# RF_STM.net
KiCad netlist of a schematic drawn in Altium Designer
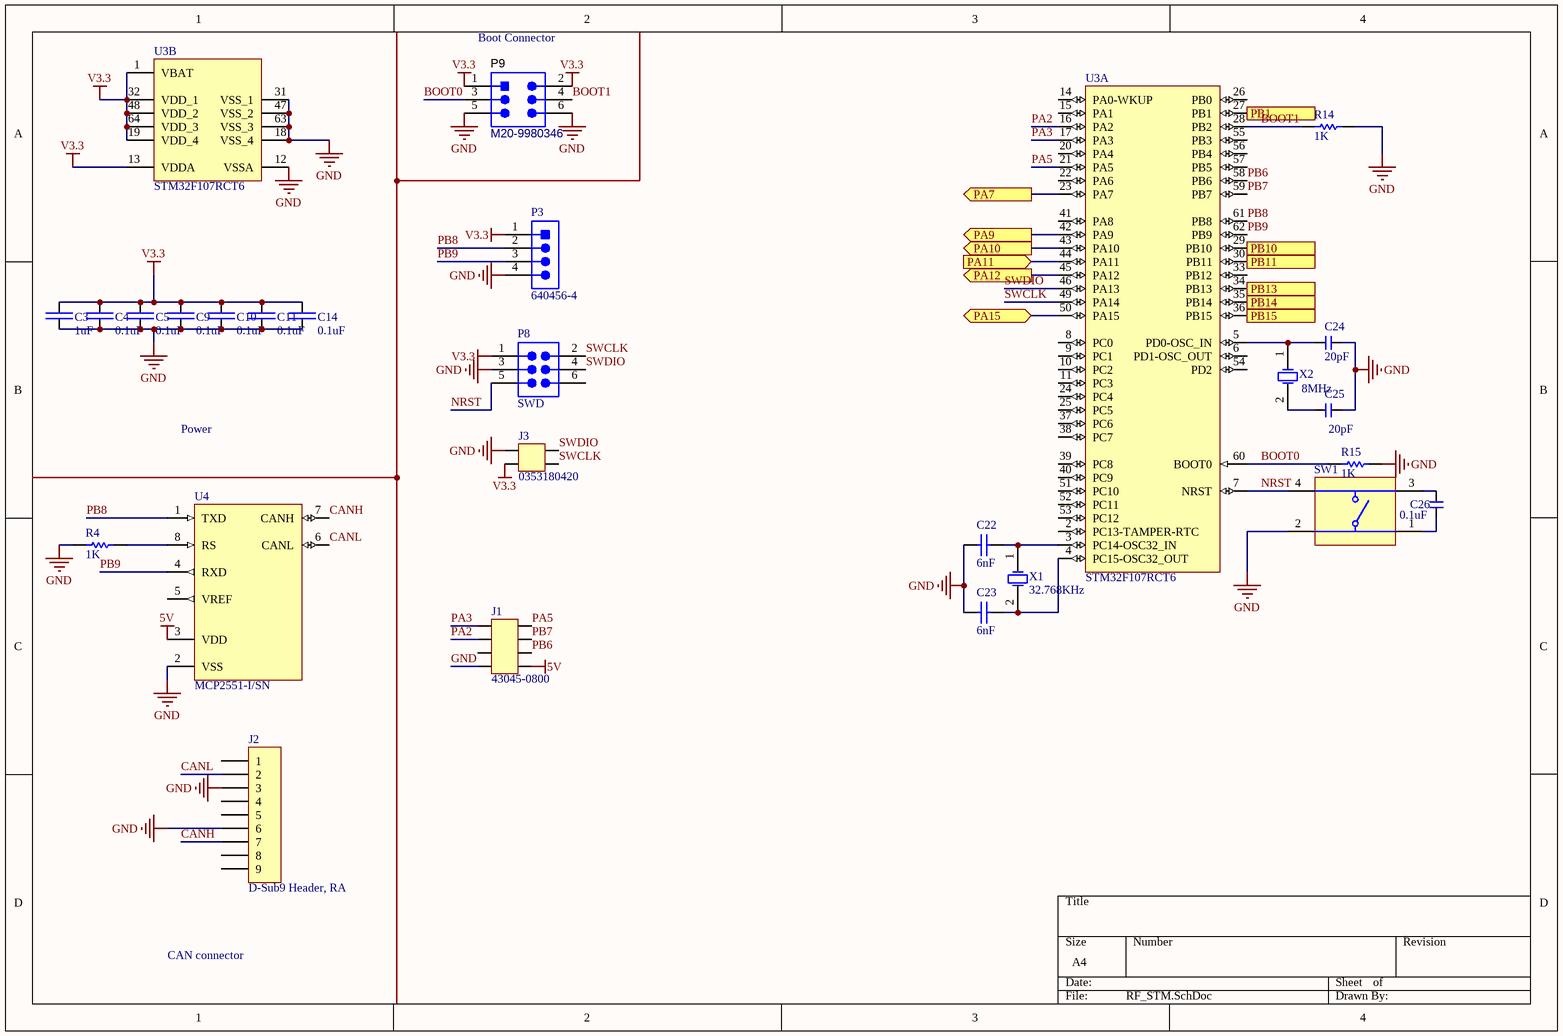
[diagram p0: RF_STM.SchDoc]

(export (version "E")
  (design (tool "Eeschema 10.0.6"))
  (components
    (comp (ref "C3")
      (value "1uF")
      (footprint "C0805")
      (description "Cap Ceramic 1uF 25V X7R 10% SMD 0805 125C T/R")
      (fields
        (field (name "MANUFACTURER") "Samsung")
        (field (name "MANUFACTURER PART NUMBER") "CL21B105KAFNNNE")
      )
      (libsource (lib "Capacitors") (part "CL21B105KAFNNNE"))
    )
    (comp (ref "C4")
      (value "0.1uF")
      (footprint "C0805")
      (description "CAP CER 0.1UF 50V X7R 0805")
      (fields
        (field (name "MANUFACTURER") "Samsung")
        (field (name "MANUFACTURER PART NUMBER") "CL21B104KBCWPNC")
      )
      (libsource (lib "Capacitors") (part "CL21B104KBCWPNC"))
    )
    (comp (ref "C5")
      (value "0.1uF")
      (footprint "C0805")
      (description "CAP CER 0.1UF 50V X7R 0805")
      (fields
        (field (name "MANUFACTURER") "Samsung")
        (field (name "MANUFACTURER PART NUMBER") "CL21B104KBCWPNC")
      )
      (libsource (lib "Capacitors") (part "CL21B104KBCWPNC"))
    )
    (comp (ref "C9")
      (value "0.1uF")
      (footprint "C0805")
      (description "CAP CER 0.1UF 50V X7R 0805")
      (fields
        (field (name "MANUFACTURER") "Samsung")
        (field (name "MANUFACTURER PART NUMBER") "CL21B104KBCWPNC")
      )
      (libsource (lib "Capacitors") (part "CL21B104KBCWPNC"))
    )
    (comp (ref "C10")
      (value "0.1uF")
      (footprint "C0805")
      (description "CAP CER 0.1UF 50V X7R 0805")
      (fields
        (field (name "MANUFACTURER") "Samsung")
        (field (name "MANUFACTURER PART NUMBER") "CL21B104KBCWPNC")
      )
      (libsource (lib "Capacitors") (part "CL21B104KBCWPNC"))
    )
    (comp (ref "C11")
      (value "0.1uF")
      (footprint "C0805")
      (description "CAP CER 0.1UF 50V X7R 0805")
      (fields
        (field (name "MANUFACTURER") "Samsung")
        (field (name "MANUFACTURER PART NUMBER") "CL21B104KBCWPNC")
      )
      (libsource (lib "Capacitors") (part "CL21B104KBCWPNC"))
    )
    (comp (ref "C14")
      (value "0.1uF")
      (footprint "C0805")
      (description "CAP CER 0.1UF 50V X7R 0805")
      (fields
        (field (name "MANUFACTURER") "Samsung")
        (field (name "MANUFACTURER PART NUMBER") "CL21B104KBCWPNC")
      )
      (libsource (lib "Capacitors") (part "CL21B104KBCWPNC"))
    )
    (comp (ref "C22")
      (value "6nF")
      (footprint "CAPC2013X140X50LL20T25")
      (description "Chip Capacitor, 2.2 uF, +/- 10%, 10 V, -55 to 85 degC, 0805 (2012 Metric), RoHS, Tape and Reel")
      (fields (field (name "MANUFACTURER") "AVX"))
      (libsource (lib "Altium Content Vault") (part "CAP-NP-2"))
    )
    (comp (ref "C23")
      (value "6nF")
      (footprint "CAPC2013X140X50LL20T25")
      (description "Chip Capacitor, 2.2 uF, +/- 10%, 10 V, -55 to 85 degC, 0805 (2012 Metric), RoHS, Tape and Reel")
      (fields (field (name "MANUFACTURER") "AVX"))
      (libsource (lib "Altium Content Vault") (part "CAP-NP-2"))
    )
    (comp (ref "C24")
      (value "20pF")
      (footprint "C0805")
      (description "CAP CER 20PF 50V C0G/NP0 0805")
      (fields
        (field (name "MANUFACTURER") "Samsung")
        (field (name "MANUFACTURER PART NUMBER") "CL21B103KBANNNC")
      )
      (libsource (lib "MCB") (part "C0805C200J5GACTU"))
    )
    (comp (ref "C25")
      (value "20pF")
      (footprint "C0805")
      (description "CAP CER 20PF 50V C0G/NP0 0805")
      (fields
        (field (name "MANUFACTURER") "Samsung")
        (field (name "MANUFACTURER PART NUMBER") "CL21B103KBANNNC")
      )
      (libsource (lib "MCB") (part "C0805C200J5GACTU"))
    )
    (comp (ref "C26")
      (value "0.1uF")
      (footprint "C0805")
      (description "CAP CER 0.1UF 50V X7R 0805")
      (fields
        (field (name "MANUFACTURER") "Samsung")
        (field (name "MANUFACTURER PART NUMBER") "CL21B104KBCWPNC")
      )
      (libsource (lib "MCB") (part "CL21B104KBCWPNC"))
    )
    (comp (ref "J1")
      (value "43045-0800")
      (footprint "Micro-Fit 3.0 8pos")
      (description "Micro-fit 3.0 8pos right-angle")
      (fields (field (name "MANUFACTURER") "Molex"))
      (libsource (lib "Connectors") (part "43045-0800"))
    )
    (comp (ref "J2")
      (value "D-Sub9 Header, RA")
      (footprint "D9 Connector")
      (description "CONN D-SUB PLUG 9POS R/A SOLDER")
      (fields
        (field (name "MANUFACTURER") "TE Connectivity")
        (field (name "MANUFACTURER PART NUMBER") "5747840-6")
      )
      (libsource (lib "Connectors") (part "5747840-6"))
    )
    (comp (ref "J3")
      (value "0353180420")
      (footprint "Mini-fit Jr. 4pos")
      (description "Conn Power HDR 4 POS 4.2mm Solder RA Thru-Hole 4 Terminal 1 Port Mini-Fit® Bag")
      (fields (field (name "MANUFACTURER") "Molex"))
      (libsource (lib "Connectors") (part "0353180420"))
    )
    (comp (ref "P3")
      (value "640456-4")
      (footprint "TECO-640456-4")
      (description "Male Header, Pitch 2.54 mm, 1 x 4 Position, Height 10.03 mm, Tail Length 3.56 mm, RoHS, Bulk")
      (fields (field (name "MANUFACTURER") "TE Connectivity"))
      (libsource (lib "Altium Content Vault") (part "CN-1P-M-R4"))
    )
    (comp (ref "P8")
      (value "SWD")
      (footprint "SMTC-TSW-103-08-X-D")
      (description "0.025\" SQ Post Header, Through-hole, Vertical, -55 to 125 degC, 2.54 mm Pitch, 6-Pin, Male, RoHS")
      (fields (field (name "MANUFACTURER") "Samtec") (field (name "PARTNUMBER") "TSW-103-08-G-D"))
      (libsource (lib "Altium Content Vault") (part "SMTC-TSW-103-08-X-D"))
    )
    (comp (ref "P9")
      (value "M20-9980346")
      (footprint "HRWN-M20-9980346_V")
      (fields (field (name "MANUFACTURER") "Harwin-Inc."))
      (libsource (lib "Altium Content Vault") (part "CN-2P-M-R6"))
    )
    (comp (ref "R4")
      (value "1K")
      (footprint "RESC1608X55X25ML10T15")
      (description "Chip Resistor, 10 KOhm, +/- 1%, 01 W, -55 to 155 degC, 0603 (1608 Metric), RoHS, Tape and Reel")
      (fields (field (name "MANUFACTURER") "Yageo") (field (name "TOLERANCE") "1%"))
      (libsource (lib "Altium Content Vault") (part "RES-2"))
    )
    (comp (ref "R14")
      (value "1K")
      (footprint "RESC2013X50X30NL20T20")
      (fields (field (name "PART NUMBER") "CRCW08051K00FKEA") (field (name "MANUFACTURER") "Vishay Dale"))
      (libsource (lib "Altium Content Vault") (part "RES"))
    )
    (comp (ref "R15")
      (value "1K")
      (footprint "RESC2013X50X30NL20T20")
      (fields (field (name "PART NUMBER") "CRCW08051K00FKEA") (field (name "MANUFACTURER") "Vishay Dale"))
      (libsource (lib "Altium Content Vault") (part "RES"))
    )
    (comp (ref "SW1")
      (value "PTS645SM43SMTR92LFS")
      (footprint "ITT-PTS645S-4_V")
      (description "6 mm Tact Switche, SPST, NO, -20 to 60 degC, 4-Pin SMT, RoHS, Tape and Reel")
      (fields (field (name "MANUFACTURER") "ITT Cannon"))
      (libsource (lib "Altium Content Vault") (part "SW-SPST-4_A"))
    )
    (comp (ref "U3")
      (value "STM32F107RCT6")
      (footprint "STM-LQFP64_M")
      (libsource (lib "Altium Content Vault") (part "MC-ARM-STM32F10X-SQ64"))
    )
    (comp (ref "U4")
      (value "MCP2551-I/SN")
      (footprint "SOIC-SN8_N")
      (description "High-Speed CAN Transceiver, 8-Pin SOIC, Industrial Temperature")
      (libsource (lib "Altium Content Vault") (part "COM-TRX-MCP2551-8"))
    )
    (comp (ref "X1")
      (value "32.768KHz")
      (footprint "ABRA-ABS07-2_V")
      (description "Crystal, 32.768 kHz, 12.5 pF, -40 to 85 degC, SMD Low Profile 3.2 x 1.5 x 0.9 mm, Tape and Reel")
      (fields (field (name "MANUFACTURER") "Abracon") (field (name "PARTNUMBER") "ABS07-32.768KHz-T"))
      (libsource (lib "Altium Content Vault") (part "ABRA-ABS07-2"))
    )
    (comp (ref "X2")
      (value "8MHz")
      (footprint "ABRA-ABM3-2_V")
      (description "Miniature Ceramic Crystal, 8 MHz, -40 to 85 degC, 2-Pin SMD, RoHS, Tape and Reel")
      (fields (field (name "MANUFACTURER") "ABRACON") (field (name "TOLERANCE") "20PPM"))
      (libsource (lib "Altium Content Vault") (part "XTAL_1-2-2"))
    )
  )
  (nets
    (net (code "1") (name "/BOOT0") (class "Default")
      (node (ref "P9") (pin "3") (pinfunction "3_3") (pintype "passive"))
      (node (ref "R15") (pin "2") (pinfunction "2_2") (pintype "passive"))
      (node (ref "U3") (pin "60") (pinfunction "BOOT0_60") (pintype "input"))
    )
    (net (code "2") (name "/BOOT1") (class "Default")
      (node (ref "P9") (pin "4") (pinfunction "4_4") (pintype "passive"))
      (node (ref "R14") (pin "2") (pinfunction "2_2") (pintype "passive"))
      (node (ref "U3") (pin "28") (pinfunction "PB2_28") (pintype "bidirectional"))
    )
    (net (code "3") (name "/CANH") (class "Default")
      (node (ref "J2") (pin "7") (pinfunction "7_7") (pintype "passive"))
      (node (ref "U4") (pin "7") (pinfunction "CANH_7") (pintype "bidirectional"))
    )
    (net (code "4") (name "/CANL") (class "Default")
      (node (ref "J2") (pin "2") (pinfunction "2_2") (pintype "passive"))
      (node (ref "U4") (pin "6") (pinfunction "CANL_6") (pintype "bidirectional"))
    )
    (net (code "5") (name "/NRST") (class "Default")
      (node (ref "P8") (pin "5") (pinfunction "5_5") (pintype "passive"))
      (node (ref "SW1") (pin "4") (pinfunction "4_4") (pintype "passive"))
      (node (ref "U3") (pin "7") (pinfunction "NRST_7") (pintype "bidirectional"))
    )
    (net (code "6") (name "/PA2") (class "Default")
      (node (ref "J1") (pin "6") (pinfunction "6_6") (pintype "passive"))
      (node (ref "U3") (pin "16") (pinfunction "PA2_16") (pintype "bidirectional"))
    )
    (net (code "7") (name "/PA3") (class "Default")
      (node (ref "J1") (pin "5") (pinfunction "5_5") (pintype "passive"))
      (node (ref "U3") (pin "17") (pinfunction "PA3_17") (pintype "bidirectional"))
    )
    (net (code "8") (name "/PA5") (class "Default")
      (node (ref "J1") (pin "1") (pinfunction "1_1") (pintype "passive"))
      (node (ref "U3") (pin "21") (pinfunction "PA5_21") (pintype "bidirectional"))
    )
    (net (code "9") (name "/PA7") (class "Default")
      (node (ref "U3") (pin "23") (pinfunction "PA7_23") (pintype "bidirectional"))
    )
    (net (code "10") (name "/PA9") (class "Default")
      (node (ref "U3") (pin "42") (pinfunction "PA9_42") (pintype "bidirectional"))
    )
    (net (code "11") (name "/PA10") (class "Default")
      (node (ref "U3") (pin "43") (pinfunction "PA10_43") (pintype "bidirectional"))
    )
    (net (code "12") (name "/PA11") (class "Default")
      (node (ref "U3") (pin "44") (pinfunction "PA11_44") (pintype "bidirectional"))
    )
    (net (code "13") (name "/PA12") (class "Default")
      (node (ref "U3") (pin "45") (pinfunction "PA12_45") (pintype "bidirectional"))
    )
    (net (code "14") (name "/PA15") (class "Default")
      (node (ref "U3") (pin "50") (pinfunction "PA15_50") (pintype "bidirectional"))
    )
    (net (code "15") (name "/PB1") (class "Default")
      (node (ref "U3") (pin "27") (pinfunction "PB1_27") (pintype "bidirectional"))
    )
    (net (code "16") (name "/PB6") (class "Default")
      (node (ref "J1") (pin "3") (pinfunction "3_3") (pintype "passive"))
      (node (ref "U3") (pin "58") (pinfunction "PB6_58") (pintype "bidirectional"))
    )
    (net (code "17") (name "/PB7") (class "Default")
      (node (ref "J1") (pin "2") (pinfunction "2_2") (pintype "passive"))
      (node (ref "U3") (pin "59") (pinfunction "PB7_59") (pintype "bidirectional"))
    )
    (net (code "18") (name "/PB8") (class "Default")
      (node (ref "P3") (pin "2") (pinfunction "2_2") (pintype "passive"))
      (node (ref "U3") (pin "61") (pinfunction "PB8_61") (pintype "bidirectional"))
      (node (ref "U4") (pin "1") (pinfunction "TXD_1") (pintype "input"))
    )
    (net (code "19") (name "/PB9") (class "Default")
      (node (ref "P3") (pin "3") (pinfunction "3_3") (pintype "passive"))
      (node (ref "U3") (pin "62") (pinfunction "PB9_62") (pintype "bidirectional"))
      (node (ref "U4") (pin "4") (pinfunction "RXD_4") (pintype "output"))
    )
    (net (code "20") (name "/PB10") (class "Default")
      (node (ref "U3") (pin "29") (pinfunction "PB10_29") (pintype "bidirectional"))
    )
    (net (code "21") (name "/PB11") (class "Default")
      (node (ref "U3") (pin "30") (pinfunction "PB11_30") (pintype "bidirectional"))
    )
    (net (code "22") (name "/PB13") (class "Default")
      (node (ref "U3") (pin "34") (pinfunction "PB13_34") (pintype "bidirectional"))
    )
    (net (code "23") (name "/PB14") (class "Default")
      (node (ref "U3") (pin "35") (pinfunction "PB14_35") (pintype "bidirectional"))
    )
    (net (code "24") (name "/PB15") (class "Default")
      (node (ref "U3") (pin "36") (pinfunction "PB15_36") (pintype "bidirectional"))
    )
    (net (code "25") (name "/SWCLK") (class "Default")
      (node (ref "J3") (pin "4") (pinfunction "4_4") (pintype "passive"))
      (node (ref "P8") (pin "2") (pinfunction "2_2") (pintype "passive"))
      (node (ref "U3") (pin "49") (pinfunction "PA14_49") (pintype "bidirectional"))
    )
    (net (code "26") (name "/SWDIO") (class "Default")
      (node (ref "J3") (pin "2") (pinfunction "2_2") (pintype "passive"))
      (node (ref "P8") (pin "4") (pinfunction "4_4") (pintype "passive"))
      (node (ref "U3") (pin "46") (pinfunction "PA13_46") (pintype "bidirectional"))
    )
    (net (code "27") (name "5V") (class "Default")
      (node (ref "J1") (pin "4") (pinfunction "4_4") (pintype "passive"))
      (node (ref "U4") (pin "3") (pinfunction "VDD_3") (pintype "power_in"))
    )
    (net (code "28") (name "GND") (class "Default")
      (node (ref "C10") (pin "2") (pinfunction "2_2") (pintype "passive"))
      (node (ref "C11") (pin "1") (pinfunction "1_1") (pintype "passive"))
      (node (ref "C14") (pin "1") (pinfunction "1_1") (pintype "passive"))
      (node (ref "C22") (pin "1") (pinfunction "1_1") (pintype "passive"))
      (node (ref "C23") (pin "1") (pinfunction "1_1") (pintype "passive"))
      (node (ref "C24") (pin "1") (pinfunction "1_1") (pintype "passive"))
      (node (ref "C25") (pin "1") (pinfunction "1_1") (pintype "passive"))
      (node (ref "C3") (pin "2") (pinfunction "2_2") (pintype "passive"))
      (node (ref "C4") (pin "1") (pinfunction "1_1") (pintype "passive"))
      (node (ref "C5") (pin "1") (pinfunction "1_1") (pintype "passive"))
      (node (ref "C9") (pin "1") (pinfunction "1_1") (pintype "passive"))
      (node (ref "J1") (pin "8") (pinfunction "8_8") (pintype "passive"))
      (node (ref "J2") (pin "3") (pinfunction "3_3") (pintype "passive"))
      (node (ref "J2") (pin "6") (pinfunction "6_6") (pintype "passive"))
      (node (ref "J3") (pin "1") (pinfunction "1_1") (pintype "passive"))
      (node (ref "P3") (pin "4") (pinfunction "4_4") (pintype "passive"))
      (node (ref "P8") (pin "3") (pinfunction "3_3") (pintype "passive"))
      (node (ref "P9") (pin "5") (pinfunction "5_5") (pintype "passive"))
      (node (ref "P9") (pin "6") (pinfunction "6_6") (pintype "passive"))
      (node (ref "R14") (pin "1") (pinfunction "1_1") (pintype "passive"))
      (node (ref "R15") (pin "1") (pinfunction "1_1") (pintype "passive"))
      (node (ref "R4") (pin "1") (pinfunction "1_1") (pintype "passive"))
      (node (ref "SW1") (pin "2") (pinfunction "2_2") (pintype "passive"))
      (node (ref "U3") (pin "12") (pinfunction "VSSA_12") (pintype "power_in"))
      (node (ref "U3") (pin "18") (pinfunction "VSS_4_18") (pintype "power_in"))
      (node (ref "U3") (pin "31") (pinfunction "VSS_1_31") (pintype "power_in"))
      (node (ref "U3") (pin "47") (pinfunction "VSS_2_47") (pintype "power_in"))
      (node (ref "U3") (pin "63") (pinfunction "VSS_3_63") (pintype "power_in"))
      (node (ref "U4") (pin "2") (pinfunction "VSS_2") (pintype "power_in"))
    )
    (net (code "29") (name "Net-(C26-Pad1)") (class "Default")
      (node (ref "C26") (pin "1") (pinfunction "1_1") (pintype "passive"))
      (node (ref "SW1") (pin "3") (pinfunction "3_3") (pintype "passive"))
    )
    (net (code "30") (name "Net-(C26-Pad2)") (class "Default")
      (node (ref "C26") (pin "2") (pinfunction "2_2") (pintype "passive"))
      (node (ref "SW1") (pin "1") (pinfunction "1_1") (pintype "passive"))
    )
    (net (code "31") (name "Net-(U3A-PC14-OSC32_IN)") (class "Default")
      (node (ref "C22") (pin "2") (pinfunction "2_2") (pintype "passive"))
      (node (ref "U3") (pin "3") (pinfunction "PC14-OSC32_IN_3") (pintype "bidirectional"))
      (node (ref "X1") (pin "1") (pinfunction "X1_1") (pintype "passive"))
    )
    (net (code "32") (name "Net-(U3A-PC15-OSC32_OUT)") (class "Default")
      (node (ref "C23") (pin "2") (pinfunction "2_2") (pintype "passive"))
      (node (ref "U3") (pin "4") (pinfunction "PC15-OSC32_OUT_4") (pintype "bidirectional"))
      (node (ref "X1") (pin "2") (pinfunction "X2_2") (pintype "passive"))
    )
    (net (code "33") (name "Net-(U3A-PD0-OSC_IN)") (class "Default")
      (node (ref "C24") (pin "2") (pinfunction "2_2") (pintype "passive"))
      (node (ref "U3") (pin "5") (pinfunction "PD0-OSC_IN_5") (pintype "bidirectional"))
      (node (ref "X2") (pin "1") (pinfunction "X1_1") (pintype "passive"))
    )
    (net (code "34") (name "Net-(U4-RS)") (class "Default")
      (node (ref "R4") (pin "2") (pinfunction "2_2") (pintype "passive"))
      (node (ref "U4") (pin "8") (pinfunction "RS_8") (pintype "input"))
    )
    (net (code "35") (name "Net-(X2-X2)") (class "Default")
      (node (ref "C25") (pin "2") (pinfunction "2_2") (pintype "passive"))
      (node (ref "X2") (pin "2") (pinfunction "X2_2") (pintype "passive"))
    )
    (net (code "36") (name "V3.3") (class "Default")
      (node (ref "C10") (pin "1") (pinfunction "1_1") (pintype "passive"))
      (node (ref "C11") (pin "2") (pinfunction "2_2") (pintype "passive"))
      (node (ref "C14") (pin "2") (pinfunction "2_2") (pintype "passive"))
      (node (ref "C3") (pin "1") (pinfunction "1_1") (pintype "passive"))
      (node (ref "C4") (pin "2") (pinfunction "2_2") (pintype "passive"))
      (node (ref "C5") (pin "2") (pinfunction "2_2") (pintype "passive"))
      (node (ref "C9") (pin "2") (pinfunction "2_2") (pintype "passive"))
      (node (ref "J3") (pin "3") (pinfunction "3_3") (pintype "passive"))
      (node (ref "P3") (pin "1") (pinfunction "1_1") (pintype "passive"))
      (node (ref "P8") (pin "1") (pinfunction "1_1") (pintype "passive"))
      (node (ref "P9") (pin "1") (pinfunction "1_1") (pintype "passive"))
      (node (ref "P9") (pin "2") (pinfunction "2_2") (pintype "passive"))
      (node (ref "U3") (pin "1") (pinfunction "VBAT_1") (pintype "power_in"))
      (node (ref "U3") (pin "13") (pinfunction "VDDA_13") (pintype "power_in"))
      (node (ref "U3") (pin "19") (pinfunction "VDD_4_19") (pintype "power_in"))
      (node (ref "U3") (pin "32") (pinfunction "VDD_1_32") (pintype "power_in"))
      (node (ref "U3") (pin "48") (pinfunction "VDD_2_48") (pintype "power_in"))
      (node (ref "U3") (pin "64") (pinfunction "VDD_3_64") (pintype "power_in"))
    )
    (net (code "37") (name "unconnected-(J1-Pad7)") (class "Default")
      (node (ref "J1") (pin "7") (pinfunction "7_7") (pintype "passive"))
    )
    (net (code "38") (name "unconnected-(J2-Pad1)") (class "Default")
      (node (ref "J2") (pin "1") (pinfunction "1_1") (pintype "passive"))
    )
    (net (code "39") (name "unconnected-(J2-Pad4)") (class "Default")
      (node (ref "J2") (pin "4") (pinfunction "4_4") (pintype "passive"))
    )
    (net (code "40") (name "unconnected-(J2-Pad5)") (class "Default")
      (node (ref "J2") (pin "5") (pinfunction "5_5") (pintype "passive"))
    )
    (net (code "41") (name "unconnected-(J2-Pad8)") (class "Default")
      (node (ref "J2") (pin "8") (pinfunction "8_8") (pintype "passive"))
    )
    (net (code "42") (name "unconnected-(J2-Pad9)") (class "Default")
      (node (ref "J2") (pin "9") (pinfunction "9_9") (pintype "passive"))
    )
    (net (code "43") (name "unconnected-(P8-Pad6)") (class "Default")
      (node (ref "P8") (pin "6") (pinfunction "6_6") (pintype "passive"))
    )
    (net (code "44") (name "unconnected-(U3A-PA0-WKUP-Pad14)") (class "Default")
      (node (ref "U3") (pin "14") (pinfunction "PA0-WKUP_14") (pintype "bidirectional"))
    )
    (net (code "45") (name "unconnected-(U3A-PA1-Pad15)") (class "Default")
      (node (ref "U3") (pin "15") (pinfunction "PA1_15") (pintype "bidirectional"))
    )
    (net (code "46") (name "unconnected-(U3A-PA4-Pad20)") (class "Default")
      (node (ref "U3") (pin "20") (pinfunction "PA4_20") (pintype "bidirectional"))
    )
    (net (code "47") (name "unconnected-(U3A-PA6-Pad22)") (class "Default")
      (node (ref "U3") (pin "22") (pinfunction "PA6_22") (pintype "bidirectional"))
    )
    (net (code "48") (name "unconnected-(U3A-PA8-Pad41)") (class "Default")
      (node (ref "U3") (pin "41") (pinfunction "PA8_41") (pintype "bidirectional"))
    )
    (net (code "49") (name "unconnected-(U3A-PB0-Pad26)") (class "Default")
      (node (ref "U3") (pin "26") (pinfunction "PB0_26") (pintype "bidirectional"))
    )
    (net (code "50") (name "unconnected-(U3A-PB3-Pad55)") (class "Default")
      (node (ref "U3") (pin "55") (pinfunction "PB3_55") (pintype "bidirectional"))
    )
    (net (code "51") (name "unconnected-(U3A-PB4-Pad56)") (class "Default")
      (node (ref "U3") (pin "56") (pinfunction "PB4_56") (pintype "bidirectional"))
    )
    (net (code "52") (name "unconnected-(U3A-PB5-Pad57)") (class "Default")
      (node (ref "U3") (pin "57") (pinfunction "PB5_57") (pintype "bidirectional"))
    )
    (net (code "53") (name "unconnected-(U3A-PB12-Pad33)") (class "Default")
      (node (ref "U3") (pin "33") (pinfunction "PB12_33") (pintype "bidirectional"))
    )
    (net (code "54") (name "unconnected-(U3A-PC0-Pad8)") (class "Default")
      (node (ref "U3") (pin "8") (pinfunction "PC0_8") (pintype "bidirectional"))
    )
    (net (code "55") (name "unconnected-(U3A-PC1-Pad9)") (class "Default")
      (node (ref "U3") (pin "9") (pinfunction "PC1_9") (pintype "bidirectional"))
    )
    (net (code "56") (name "unconnected-(U3A-PC2-Pad10)") (class "Default")
      (node (ref "U3") (pin "10") (pinfunction "PC2_10") (pintype "bidirectional"))
    )
    (net (code "57") (name "unconnected-(U3A-PC3-Pad11)") (class "Default")
      (node (ref "U3") (pin "11") (pinfunction "PC3_11") (pintype "bidirectional"))
    )
    (net (code "58") (name "unconnected-(U3A-PC4-Pad24)") (class "Default")
      (node (ref "U3") (pin "24") (pinfunction "PC4_24") (pintype "bidirectional"))
    )
    (net (code "59") (name "unconnected-(U3A-PC5-Pad25)") (class "Default")
      (node (ref "U3") (pin "25") (pinfunction "PC5_25") (pintype "bidirectional"))
    )
    (net (code "60") (name "unconnected-(U3A-PC6-Pad37)") (class "Default")
      (node (ref "U3") (pin "37") (pinfunction "PC6_37") (pintype "bidirectional"))
    )
    (net (code "61") (name "unconnected-(U3A-PC7-Pad38)") (class "Default")
      (node (ref "U3") (pin "38") (pinfunction "PC7_38") (pintype "bidirectional"))
    )
    (net (code "62") (name "unconnected-(U3A-PC8-Pad39)") (class "Default")
      (node (ref "U3") (pin "39") (pinfunction "PC8_39") (pintype "bidirectional"))
    )
    (net (code "63") (name "unconnected-(U3A-PC9-Pad40)") (class "Default")
      (node (ref "U3") (pin "40") (pinfunction "PC9_40") (pintype "bidirectional"))
    )
    (net (code "64") (name "unconnected-(U3A-PC10-Pad51)") (class "Default")
      (node (ref "U3") (pin "51") (pinfunction "PC10_51") (pintype "bidirectional"))
    )
    (net (code "65") (name "unconnected-(U3A-PC11-Pad52)") (class "Default")
      (node (ref "U3") (pin "52") (pinfunction "PC11_52") (pintype "bidirectional"))
    )
    (net (code "66") (name "unconnected-(U3A-PC12-Pad53)") (class "Default")
      (node (ref "U3") (pin "53") (pinfunction "PC12_53") (pintype "bidirectional"))
    )
    (net (code "67") (name "unconnected-(U3A-PC13-TAMPER-RTC-Pad2)") (class "Default")
      (node (ref "U3") (pin "2") (pinfunction "PC13-TAMPER-RTC_2") (pintype "bidirectional"))
    )
    (net (code "68") (name "unconnected-(U3A-PD1-OSC_OUT-Pad6)") (class "Default")
      (node (ref "U3") (pin "6") (pinfunction "PD1-OSC_OUT_6") (pintype "bidirectional"))
    )
    (net (code "69") (name "unconnected-(U3A-PD2-Pad54)") (class "Default")
      (node (ref "U3") (pin "54") (pinfunction "PD2_54") (pintype "bidirectional"))
    )
    (net (code "70") (name "unconnected-(U4-VREF-Pad5)") (class "Default")
      (node (ref "U4") (pin "5") (pinfunction "VREF_5") (pintype "output"))
    )
  )
)
